# Angle_board.net
KiCad netlist of a schematic drawn in EAGLE
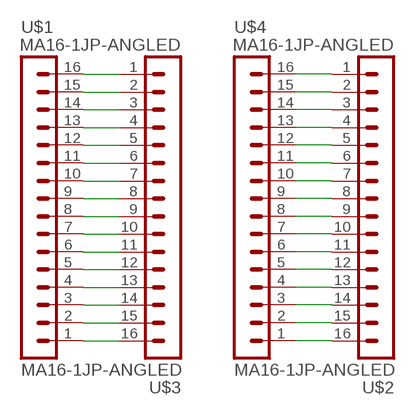
[diagram p0: schematic, sheet 1]

(export (version "E")
  (design (tool "Eeschema 10.0.6"))
  (components
    (comp (ref "U$1")
      (value "MA16-1JP-ANGLED")
      (footprint "eagle-import:SIP-PIN16-1J")
      (libsource (lib "eagle-import") (part "MA16-1JP"))
    )
    (comp (ref "U$2")
      (value "MA16-1JP-ANGLED")
      (footprint "eagle-import:SIP-PIN16-1J")
      (libsource (lib "eagle-import") (part "MA16-1JP"))
    )
    (comp (ref "U$3")
      (value "MA16-1JP-ANGLED")
      (footprint "eagle-import:SIP-PIN16-1J")
      (libsource (lib "eagle-import") (part "MA16-1JP"))
    )
    (comp (ref "U$4")
      (value "MA16-1JP-ANGLED")
      (footprint "eagle-import:SIP-PIN16-1J")
      (libsource (lib "eagle-import") (part "MA16-1JP"))
    )
  )
  (nets
    (net (code "1") (name "/AGND") (class "Default")
      (node (ref "U$1") (pin "7") (pinfunction "7_7") (pintype "passive"))
      (node (ref "U$2") (pin "4") (pinfunction "4_4") (pintype "passive"))
      (node (ref "U$3") (pin "10") (pinfunction "10_10") (pintype "passive"))
      (node (ref "U$4") (pin "13") (pinfunction "13_13") (pintype "passive"))
    )
    (net (code "2") (name "Net-(U$1-Pad1)") (class "Default")
      (node (ref "U$1") (pin "1") (pinfunction "1_1") (pintype "passive"))
      (node (ref "U$3") (pin "16") (pinfunction "16_16") (pintype "passive"))
    )
    (net (code "3") (name "Net-(U$1-Pad2)") (class "Default")
      (node (ref "U$1") (pin "2") (pinfunction "2_2") (pintype "passive"))
      (node (ref "U$3") (pin "15") (pinfunction "15_15") (pintype "passive"))
    )
    (net (code "4") (name "Net-(U$1-Pad3)") (class "Default")
      (node (ref "U$1") (pin "3") (pinfunction "3_3") (pintype "passive"))
      (node (ref "U$3") (pin "14") (pinfunction "14_14") (pintype "passive"))
    )
    (net (code "5") (name "Net-(U$1-Pad4)") (class "Default")
      (node (ref "U$1") (pin "4") (pinfunction "4_4") (pintype "passive"))
      (node (ref "U$3") (pin "13") (pinfunction "13_13") (pintype "passive"))
    )
    (net (code "6") (name "Net-(U$1-Pad5)") (class "Default")
      (node (ref "U$1") (pin "5") (pinfunction "5_5") (pintype "passive"))
      (node (ref "U$3") (pin "12") (pinfunction "12_12") (pintype "passive"))
    )
    (net (code "7") (name "Net-(U$1-Pad6)") (class "Default")
      (node (ref "U$1") (pin "6") (pinfunction "6_6") (pintype "passive"))
      (node (ref "U$3") (pin "11") (pinfunction "11_11") (pintype "passive"))
    )
    (net (code "8") (name "Net-(U$1-Pad8)") (class "Default")
      (node (ref "U$1") (pin "8") (pinfunction "8_8") (pintype "passive"))
      (node (ref "U$3") (pin "9") (pinfunction "9_9") (pintype "passive"))
    )
    (net (code "9") (name "Net-(U$1-Pad9)") (class "Default")
      (node (ref "U$1") (pin "9") (pinfunction "9_9") (pintype "passive"))
      (node (ref "U$3") (pin "8") (pinfunction "8_8") (pintype "passive"))
    )
    (net (code "10") (name "Net-(U$1-Pad10)") (class "Default")
      (node (ref "U$1") (pin "10") (pinfunction "10_10") (pintype "passive"))
      (node (ref "U$3") (pin "7") (pinfunction "7_7") (pintype "passive"))
    )
    (net (code "11") (name "Net-(U$1-Pad11)") (class "Default")
      (node (ref "U$1") (pin "11") (pinfunction "11_11") (pintype "passive"))
      (node (ref "U$3") (pin "6") (pinfunction "6_6") (pintype "passive"))
    )
    (net (code "12") (name "Net-(U$1-Pad12)") (class "Default")
      (node (ref "U$1") (pin "12") (pinfunction "12_12") (pintype "passive"))
      (node (ref "U$3") (pin "5") (pinfunction "5_5") (pintype "passive"))
    )
    (net (code "13") (name "Net-(U$1-Pad13)") (class "Default")
      (node (ref "U$1") (pin "13") (pinfunction "13_13") (pintype "passive"))
      (node (ref "U$3") (pin "4") (pinfunction "4_4") (pintype "passive"))
    )
    (net (code "14") (name "Net-(U$1-Pad14)") (class "Default")
      (node (ref "U$1") (pin "14") (pinfunction "14_14") (pintype "passive"))
      (node (ref "U$3") (pin "3") (pinfunction "3_3") (pintype "passive"))
    )
    (net (code "15") (name "Net-(U$1-Pad15)") (class "Default")
      (node (ref "U$1") (pin "15") (pinfunction "15_15") (pintype "passive"))
      (node (ref "U$3") (pin "2") (pinfunction "2_2") (pintype "passive"))
    )
    (net (code "16") (name "Net-(U$1-Pad16)") (class "Default")
      (node (ref "U$1") (pin "16") (pinfunction "16_16") (pintype "passive"))
      (node (ref "U$3") (pin "1") (pinfunction "1_1") (pintype "passive"))
    )
    (net (code "17") (name "Net-(U$2-Pad1)") (class "Default")
      (node (ref "U$2") (pin "1") (pinfunction "1_1") (pintype "passive"))
      (node (ref "U$4") (pin "16") (pinfunction "16_16") (pintype "passive"))
    )
    (net (code "18") (name "Net-(U$2-Pad2)") (class "Default")
      (node (ref "U$2") (pin "2") (pinfunction "2_2") (pintype "passive"))
      (node (ref "U$4") (pin "15") (pinfunction "15_15") (pintype "passive"))
    )
    (net (code "19") (name "Net-(U$2-Pad3)") (class "Default")
      (node (ref "U$2") (pin "3") (pinfunction "3_3") (pintype "passive"))
      (node (ref "U$4") (pin "14") (pinfunction "14_14") (pintype "passive"))
    )
    (net (code "20") (name "Net-(U$2-Pad5)") (class "Default")
      (node (ref "U$2") (pin "5") (pinfunction "5_5") (pintype "passive"))
      (node (ref "U$4") (pin "12") (pinfunction "12_12") (pintype "passive"))
    )
    (net (code "21") (name "Net-(U$2-Pad6)") (class "Default")
      (node (ref "U$2") (pin "6") (pinfunction "6_6") (pintype "passive"))
      (node (ref "U$4") (pin "11") (pinfunction "11_11") (pintype "passive"))
    )
    (net (code "22") (name "Net-(U$2-Pad7)") (class "Default")
      (node (ref "U$2") (pin "7") (pinfunction "7_7") (pintype "passive"))
      (node (ref "U$4") (pin "10") (pinfunction "10_10") (pintype "passive"))
    )
    (net (code "23") (name "Net-(U$2-Pad8)") (class "Default")
      (node (ref "U$2") (pin "8") (pinfunction "8_8") (pintype "passive"))
      (node (ref "U$4") (pin "9") (pinfunction "9_9") (pintype "passive"))
    )
    (net (code "24") (name "Net-(U$2-Pad9)") (class "Default")
      (node (ref "U$2") (pin "9") (pinfunction "9_9") (pintype "passive"))
      (node (ref "U$4") (pin "8") (pinfunction "8_8") (pintype "passive"))
    )
    (net (code "25") (name "Net-(U$2-Pad10)") (class "Default")
      (node (ref "U$2") (pin "10") (pinfunction "10_10") (pintype "passive"))
      (node (ref "U$4") (pin "7") (pinfunction "7_7") (pintype "passive"))
    )
    (net (code "26") (name "Net-(U$2-Pad11)") (class "Default")
      (node (ref "U$2") (pin "11") (pinfunction "11_11") (pintype "passive"))
      (node (ref "U$4") (pin "6") (pinfunction "6_6") (pintype "passive"))
    )
    (net (code "27") (name "Net-(U$2-Pad12)") (class "Default")
      (node (ref "U$2") (pin "12") (pinfunction "12_12") (pintype "passive"))
      (node (ref "U$4") (pin "5") (pinfunction "5_5") (pintype "passive"))
    )
    (net (code "28") (name "Net-(U$2-Pad13)") (class "Default")
      (node (ref "U$2") (pin "13") (pinfunction "13_13") (pintype "passive"))
      (node (ref "U$4") (pin "4") (pinfunction "4_4") (pintype "passive"))
    )
    (net (code "29") (name "Net-(U$2-Pad14)") (class "Default")
      (node (ref "U$2") (pin "14") (pinfunction "14_14") (pintype "passive"))
      (node (ref "U$4") (pin "3") (pinfunction "3_3") (pintype "passive"))
    )
    (net (code "30") (name "Net-(U$2-Pad15)") (class "Default")
      (node (ref "U$2") (pin "15") (pinfunction "15_15") (pintype "passive"))
      (node (ref "U$4") (pin "2") (pinfunction "2_2") (pintype "passive"))
    )
    (net (code "31") (name "Net-(U$2-Pad16)") (class "Default")
      (node (ref "U$2") (pin "16") (pinfunction "16_16") (pintype "passive"))
      (node (ref "U$4") (pin "1") (pinfunction "1_1") (pintype "passive"))
    )
  )
)
